# zero_board.net
KiCad netlist of a schematic drawn in EAGLE
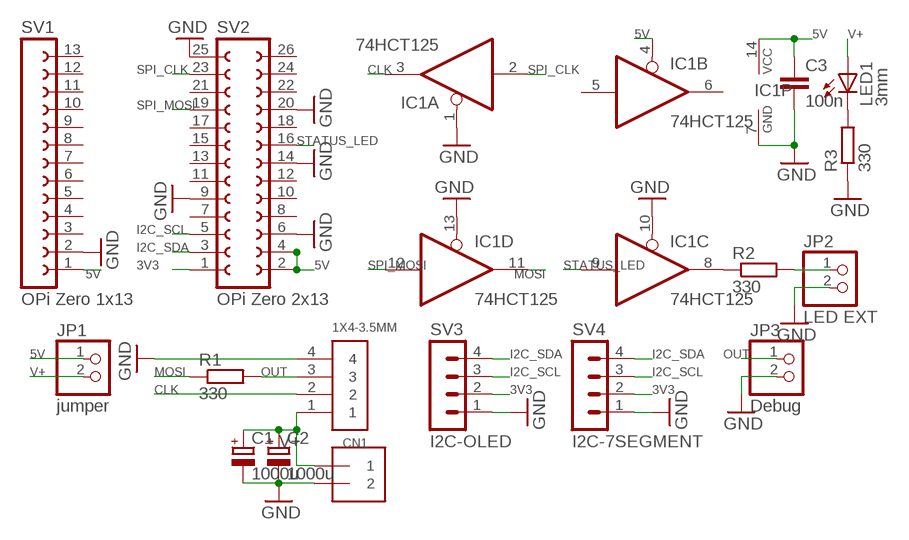
[diagram p0: schematic, sheet 1]

(export (version "E")
  (design (tool "Eeschema 10.0.6"))
  (components
    (comp (ref "C1")
      (value "1000u")
      (footprint "eagle-import:E5-6")
      (libsource (lib "eagle-import") (part "CPOL-EUE5-6"))
    )
    (comp (ref "C2")
      (value "1000u")
      (footprint "eagle-import:E5-6")
      (libsource (lib "eagle-import") (part "CPOL-EUE5-6"))
    )
    (comp (ref "C3")
      (value "100n")
      (footprint "eagle-import:C050-024X044")
      (libsource (lib "eagle-import") (part "C-EU050-024X044"))
    )
    (comp (ref "CN1")
      (value "1X4-3.5MM")
      (footprint "eagle-import:1X04-3.5MM")
      (libsource (lib "eagle-import") (part "1X4-3.5MM"))
    )
    (comp (ref "IC1")
      (value "74HCT125")
      (footprint "eagle-import:DIL14")
      (libsource (lib "eagle-import") (part "74125NHCT"))
    )
    (comp (ref "J1")
      (value "1X2-3.5MM")
      (footprint "eagle-import:1X2-3.5MM")
      (libsource (lib "eagle-import") (part "1X2-3.5MM"))
    )
    (comp (ref "JP1")
      (value "jumper")
      (footprint "eagle-import:1X02")
      (libsource (lib "eagle-import") (part "PINHD-1X2"))
    )
    (comp (ref "JP2")
      (value "LED EXT")
      (footprint "eagle-import:1X02")
      (libsource (lib "eagle-import") (part "PINHD-1X2"))
    )
    (comp (ref "JP3")
      (value "Debug")
      (footprint "eagle-import:1X02")
      (libsource (lib "eagle-import") (part "PINHD-1X2"))
    )
    (comp (ref "LED1")
      (value "3mm")
      (footprint "eagle-import:LED3MM")
      (libsource (lib "eagle-import") (part "LED3MM"))
    )
    (comp (ref "R1")
      (value "330")
      (footprint "eagle-import:0204V")
      (libsource (lib "eagle-import") (part "R-EU_0204/2V"))
    )
    (comp (ref "R2")
      (value "330")
      (footprint "eagle-import:0204V")
      (libsource (lib "eagle-import") (part "R-EU_0204/2V"))
    )
    (comp (ref "R3")
      (value "330")
      (footprint "eagle-import:0204V")
      (libsource (lib "eagle-import") (part "R-EU_0204/2V"))
    )
    (comp (ref "SV1")
      (value "OPi Zero 1x13")
      (footprint "eagle-import:FE13")
      (libsource (lib "eagle-import") (part "FE13-1"))
    )
    (comp (ref "SV2")
      (value "OPi Zero 2x13")
      (footprint "eagle-import:FE13-2")
      (libsource (lib "eagle-import") (part "FE13-2"))
    )
    (comp (ref "SV3")
      (value "I2C-OLED")
      (footprint "eagle-import:MA04-1")
      (libsource (lib "eagle-import") (part "MA04-1"))
    )
    (comp (ref "SV4")
      (value "I2C-7SEGMENT")
      (footprint "eagle-import:MA04-1")
      (libsource (lib "eagle-import") (part "MA04-1"))
    )
  )
  (nets
    (net (code "1") (name "/3V3") (class "Default")
      (node (ref "SV2") (pin "1") (pinfunction "1_1") (pintype "passive"))
      (node (ref "SV3") (pin "2") (pinfunction "2_2") (pintype "passive"))
      (node (ref "SV4") (pin "2") (pinfunction "2_2") (pintype "passive"))
    )
    (net (code "2") (name "/5V") (class "Default")
      (node (ref "C3") (pin "1") (pinfunction "1_1") (pintype "passive"))
      (node (ref "IC1") (pin "14") (pinfunction "VCC_14") (pintype "power_in"))
      (node (ref "IC1") (pin "4") (pinfunction "OE_4") (pintype "input"))
      (node (ref "JP1") (pin "1") (pinfunction "1_1") (pintype "passive"))
      (node (ref "SV1") (pin "1") (pinfunction "1_1") (pintype "passive"))
      (node (ref "SV2") (pin "2") (pinfunction "2_2") (pintype "passive"))
      (node (ref "SV2") (pin "4") (pinfunction "4_4") (pintype "passive"))
    )
    (net (code "3") (name "/CLK") (class "Default")
      (node (ref "CN1") (pin "2") (pinfunction "2_2") (pintype "bidirectional"))
      (node (ref "IC1") (pin "3") (pinfunction "O_3") (pintype "tri_state"))
    )
    (net (code "4") (name "/I2C_SCL") (class "Default")
      (node (ref "SV2") (pin "5") (pinfunction "5_5") (pintype "passive"))
      (node (ref "SV3") (pin "3") (pinfunction "3_3") (pintype "passive"))
      (node (ref "SV4") (pin "3") (pinfunction "3_3") (pintype "passive"))
    )
    (net (code "5") (name "/I2C_SDA") (class "Default")
      (node (ref "SV2") (pin "3") (pinfunction "3_3") (pintype "passive"))
      (node (ref "SV3") (pin "4") (pinfunction "4_4") (pintype "passive"))
      (node (ref "SV4") (pin "4") (pinfunction "4_4") (pintype "passive"))
    )
    (net (code "6") (name "/MOSI") (class "Default")
      (node (ref "IC1") (pin "11") (pinfunction "O_11") (pintype "tri_state"))
      (node (ref "R1") (pin "1") (pinfunction "1_1") (pintype "passive"))
    )
    (net (code "7") (name "/OUT") (class "Default")
      (node (ref "CN1") (pin "3") (pinfunction "3_3") (pintype "bidirectional"))
      (node (ref "JP3") (pin "1") (pinfunction "1_1") (pintype "passive"))
      (node (ref "R1") (pin "2") (pinfunction "2_2") (pintype "passive"))
    )
    (net (code "8") (name "/SPI_CLK") (class "Default")
      (node (ref "IC1") (pin "2") (pinfunction "I_2") (pintype "input"))
      (node (ref "SV2") (pin "23") (pinfunction "23_23") (pintype "passive"))
    )
    (net (code "9") (name "/SPI_MOSI") (class "Default")
      (node (ref "IC1") (pin "12") (pinfunction "I_12") (pintype "input"))
      (node (ref "SV2") (pin "19") (pinfunction "19_19") (pintype "passive"))
    )
    (net (code "10") (name "/STATUS_LED") (class "Default")
      (node (ref "IC1") (pin "9") (pinfunction "I_9") (pintype "input"))
      (node (ref "SV2") (pin "16") (pinfunction "16_16") (pintype "passive"))
    )
    (net (code "11") (name "/V+") (class "Default")
      (node (ref "C1") (pin "+") (pinfunction "+_+") (pintype "passive"))
      (node (ref "C2") (pin "+") (pinfunction "+_+") (pintype "passive"))
      (node (ref "CN1") (pin "1") (pinfunction "1_1") (pintype "bidirectional"))
      (node (ref "J1") (pin "1") (pinfunction "1_1") (pintype "passive"))
      (node (ref "JP1") (pin "2") (pinfunction "2_2") (pintype "passive"))
      (node (ref "LED1") (pin "A") (pinfunction "A_A") (pintype "passive"))
    )
    (net (code "12") (name "GND") (class "Default")
      (node (ref "C1") (pin "-") (pinfunction "-_-") (pintype "passive"))
      (node (ref "C2") (pin "-") (pinfunction "-_-") (pintype "passive"))
      (node (ref "C3") (pin "2") (pinfunction "2_2") (pintype "passive"))
      (node (ref "CN1") (pin "4") (pinfunction "4_4") (pintype "bidirectional"))
      (node (ref "IC1") (pin "1") (pinfunction "OE_1") (pintype "input"))
      (node (ref "IC1") (pin "10") (pinfunction "OE_10") (pintype "input"))
      (node (ref "IC1") (pin "13") (pinfunction "OE_13") (pintype "input"))
      (node (ref "IC1") (pin "7") (pinfunction "GND_7") (pintype "power_in"))
      (node (ref "J1") (pin "2") (pinfunction "2_2") (pintype "passive"))
      (node (ref "JP2") (pin "2") (pinfunction "2_2") (pintype "passive"))
      (node (ref "JP3") (pin "2") (pinfunction "2_2") (pintype "passive"))
      (node (ref "R3") (pin "1") (pinfunction "1_1") (pintype "passive"))
      (node (ref "SV1") (pin "2") (pinfunction "2_2") (pintype "passive"))
      (node (ref "SV2") (pin "14") (pinfunction "14_14") (pintype "passive"))
      (node (ref "SV2") (pin "20") (pinfunction "20_20") (pintype "passive"))
      (node (ref "SV2") (pin "25") (pinfunction "25_25") (pintype "passive"))
      (node (ref "SV2") (pin "6") (pinfunction "6_6") (pintype "passive"))
      (node (ref "SV2") (pin "9") (pinfunction "9_9") (pintype "passive"))
      (node (ref "SV3") (pin "1") (pinfunction "1_1") (pintype "passive"))
      (node (ref "SV4") (pin "1") (pinfunction "1_1") (pintype "passive"))
    )
    (net (code "13") (name "Net-(IC1C-O)") (class "Default")
      (node (ref "IC1") (pin "8") (pinfunction "O_8") (pintype "tri_state"))
      (node (ref "R2") (pin "1") (pinfunction "1_1") (pintype "passive"))
    )
    (net (code "14") (name "Net-(JP2-Pad1)") (class "Default")
      (node (ref "JP2") (pin "1") (pinfunction "1_1") (pintype "passive"))
      (node (ref "R2") (pin "2") (pinfunction "2_2") (pintype "passive"))
    )
    (net (code "15") (name "Net-(LED1-C)") (class "Default")
      (node (ref "LED1") (pin "K") (pinfunction "C_K") (pintype "passive"))
      (node (ref "R3") (pin "2") (pinfunction "2_2") (pintype "passive"))
    )
    (net (code "16") (name "unconnected-(IC1B-I-Pad5)") (class "Default")
      (node (ref "IC1") (pin "5") (pinfunction "I_5") (pintype "input"))
    )
    (net (code "17") (name "unconnected-(IC1B-O-Pad6)") (class "Default")
      (node (ref "IC1") (pin "6") (pinfunction "O_6") (pintype "tri_state"))
    )
    (net (code "18") (name "unconnected-(SV1-Pad3)") (class "Default")
      (node (ref "SV1") (pin "3") (pinfunction "3_3") (pintype "passive"))
    )
    (net (code "19") (name "unconnected-(SV1-Pad4)") (class "Default")
      (node (ref "SV1") (pin "4") (pinfunction "4_4") (pintype "passive"))
    )
    (net (code "20") (name "unconnected-(SV1-Pad5)") (class "Default")
      (node (ref "SV1") (pin "5") (pinfunction "5_5") (pintype "passive"))
    )
    (net (code "21") (name "unconnected-(SV1-Pad6)") (class "Default")
      (node (ref "SV1") (pin "6") (pinfunction "6_6") (pintype "passive"))
    )
    (net (code "22") (name "unconnected-(SV1-Pad7)") (class "Default")
      (node (ref "SV1") (pin "7") (pinfunction "7_7") (pintype "passive"))
    )
    (net (code "23") (name "unconnected-(SV1-Pad8)") (class "Default")
      (node (ref "SV1") (pin "8") (pinfunction "8_8") (pintype "passive"))
    )
    (net (code "24") (name "unconnected-(SV1-Pad9)") (class "Default")
      (node (ref "SV1") (pin "9") (pinfunction "9_9") (pintype "passive"))
    )
    (net (code "25") (name "unconnected-(SV1-Pad10)") (class "Default")
      (node (ref "SV1") (pin "10") (pinfunction "10_10") (pintype "passive"))
    )
    (net (code "26") (name "unconnected-(SV1-Pad11)") (class "Default")
      (node (ref "SV1") (pin "11") (pinfunction "11_11") (pintype "passive"))
    )
    (net (code "27") (name "unconnected-(SV1-Pad12)") (class "Default")
      (node (ref "SV1") (pin "12") (pinfunction "12_12") (pintype "passive"))
    )
    (net (code "28") (name "unconnected-(SV1-Pad13)") (class "Default")
      (node (ref "SV1") (pin "13") (pinfunction "13_13") (pintype "passive"))
    )
    (net (code "29") (name "unconnected-(SV2-Pad7)") (class "Default")
      (node (ref "SV2") (pin "7") (pinfunction "7_7") (pintype "passive"))
    )
    (net (code "30") (name "unconnected-(SV2-Pad8)") (class "Default")
      (node (ref "SV2") (pin "8") (pinfunction "8_8") (pintype "passive"))
    )
    (net (code "31") (name "unconnected-(SV2-Pad10)") (class "Default")
      (node (ref "SV2") (pin "10") (pinfunction "10_10") (pintype "passive"))
    )
    (net (code "32") (name "unconnected-(SV2-Pad11)") (class "Default")
      (node (ref "SV2") (pin "11") (pinfunction "11_11") (pintype "passive"))
    )
    (net (code "33") (name "unconnected-(SV2-Pad12)") (class "Default")
      (node (ref "SV2") (pin "12") (pinfunction "12_12") (pintype "passive"))
    )
    (net (code "34") (name "unconnected-(SV2-Pad13)") (class "Default")
      (node (ref "SV2") (pin "13") (pinfunction "13_13") (pintype "passive"))
    )
    (net (code "35") (name "unconnected-(SV2-Pad15)") (class "Default")
      (node (ref "SV2") (pin "15") (pinfunction "15_15") (pintype "passive"))
    )
    (net (code "36") (name "unconnected-(SV2-Pad17)") (class "Default")
      (node (ref "SV2") (pin "17") (pinfunction "17_17") (pintype "passive"))
    )
    (net (code "37") (name "unconnected-(SV2-Pad18)") (class "Default")
      (node (ref "SV2") (pin "18") (pinfunction "18_18") (pintype "passive"))
    )
    (net (code "38") (name "unconnected-(SV2-Pad21)") (class "Default")
      (node (ref "SV2") (pin "21") (pinfunction "21_21") (pintype "passive"))
    )
    (net (code "39") (name "unconnected-(SV2-Pad22)") (class "Default")
      (node (ref "SV2") (pin "22") (pinfunction "22_22") (pintype "passive"))
    )
    (net (code "40") (name "unconnected-(SV2-Pad24)") (class "Default")
      (node (ref "SV2") (pin "24") (pinfunction "24_24") (pintype "passive"))
    )
    (net (code "41") (name "unconnected-(SV2-Pad26)") (class "Default")
      (node (ref "SV2") (pin "26") (pinfunction "26_26") (pintype "passive"))
    )
  )
)
